# Input_Connector.net
KiCad netlist of a schematic drawn in Altium Designer
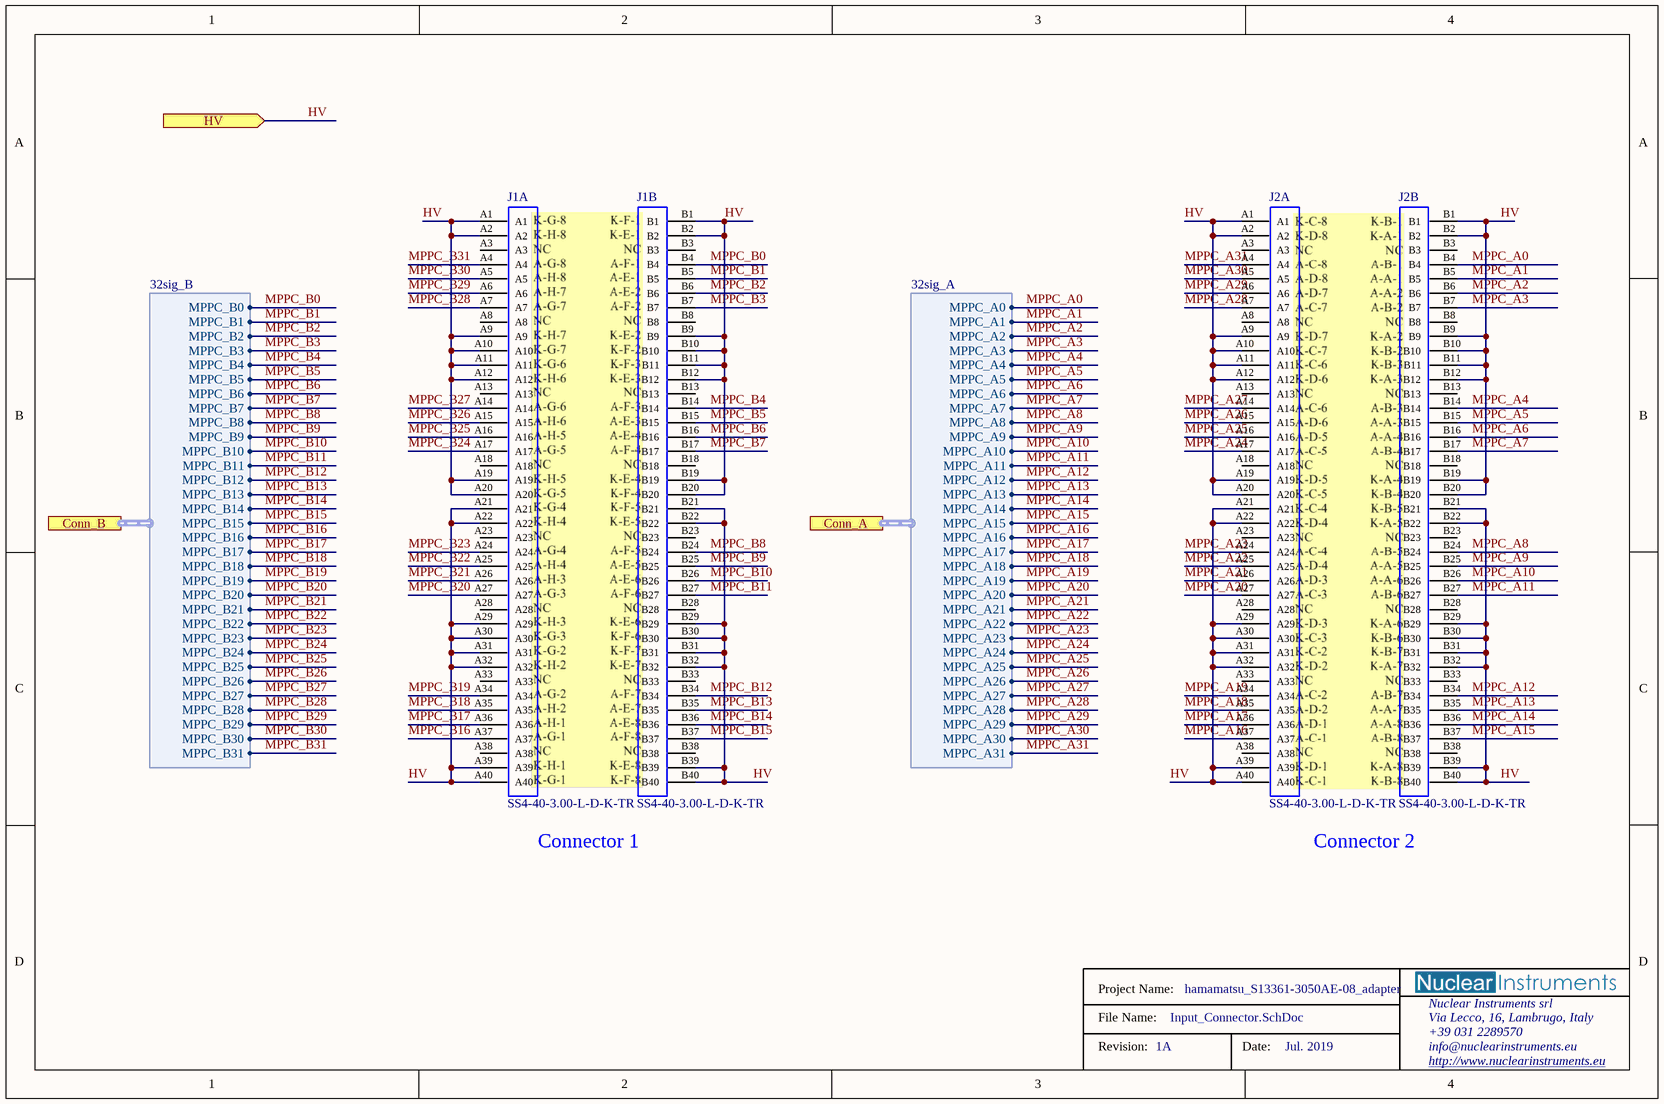
[diagram p0: Input_Connector.SchDoc]

(export (version "E")
  (design (tool "Eeschema 10.0.6"))
  (components
    (comp (ref "J1")
      (value "SS4-40-3.00-L-D-K-TR")
      (footprint "Samtec_SS4-40-3.00-L-D-K-TR")
      (description "ULTRA FINE PITCH SOCKET")
      (libsource (lib "Board_Board_Connectors__SARAversion-64") (part "Samtec_SS4-40-3.00-L-D-K-TR"))
    )
    (comp (ref "J2")
      (value "SS4-40-3.00-L-D-K-TR")
      (footprint "Samtec_SS4-40-3.00-L-D-K-TR")
      (description "ULTRA FINE PITCH SOCKET")
      (libsource (lib "Board_Board_Connectors__SARAversion-64") (part "Samtec_SS4-40-3.00-L-D-K-TR"))
    )
  )
  (nets
    (net (code "3") (name "/HV") (class "Default")
      (node (ref "J1") (pin "A1") (pinfunction "A1_A1") (pintype "passive"))
      (node (ref "J1") (pin "A10") (pinfunction "A10_A10") (pintype "passive"))
      (node (ref "J1") (pin "A11") (pinfunction "A11_A11") (pintype "passive"))
      (node (ref "J1") (pin "A12") (pinfunction "A12_A12") (pintype "passive"))
      (node (ref "J1") (pin "A19") (pinfunction "A19_A19") (pintype "passive"))
      (node (ref "J1") (pin "A2") (pinfunction "A2_A2") (pintype "passive"))
      (node (ref "J1") (pin "A20") (pinfunction "A20_A20") (pintype "passive"))
      (node (ref "J1") (pin "A21") (pinfunction "A21_A21") (pintype "passive"))
      (node (ref "J1") (pin "A22") (pinfunction "A22_A22") (pintype "passive"))
      (node (ref "J1") (pin "A29") (pinfunction "A29_A29") (pintype "passive"))
      (node (ref "J1") (pin "A30") (pinfunction "A30_A30") (pintype "passive"))
      (node (ref "J1") (pin "A31") (pinfunction "A31_A31") (pintype "passive"))
      (node (ref "J1") (pin "A32") (pinfunction "A32_A32") (pintype "passive"))
      (node (ref "J1") (pin "A39") (pinfunction "A39_A39") (pintype "passive"))
      (node (ref "J1") (pin "A40") (pinfunction "A40_A40") (pintype "passive"))
      (node (ref "J1") (pin "A9") (pinfunction "A9_A9") (pintype "passive"))
      (node (ref "J1") (pin "B1") (pinfunction "B1_B1") (pintype "passive"))
      (node (ref "J1") (pin "B10") (pinfunction "B10_B10") (pintype "passive"))
      (node (ref "J1") (pin "B11") (pinfunction "B11_B11") (pintype "passive"))
      (node (ref "J1") (pin "B12") (pinfunction "B12_B12") (pintype "passive"))
      (node (ref "J1") (pin "B19") (pinfunction "B19_B19") (pintype "passive"))
      (node (ref "J1") (pin "B2") (pinfunction "B2_B2") (pintype "passive"))
      (node (ref "J1") (pin "B20") (pinfunction "B20_B20") (pintype "passive"))
      (node (ref "J1") (pin "B21") (pinfunction "B21_B21") (pintype "passive"))
      (node (ref "J1") (pin "B22") (pinfunction "B22_B22") (pintype "passive"))
      (node (ref "J1") (pin "B29") (pinfunction "B29_B29") (pintype "passive"))
      (node (ref "J1") (pin "B30") (pinfunction "B30_B30") (pintype "passive"))
      (node (ref "J1") (pin "B31") (pinfunction "B31_B31") (pintype "passive"))
      (node (ref "J1") (pin "B32") (pinfunction "B32_B32") (pintype "passive"))
      (node (ref "J1") (pin "B39") (pinfunction "B39_B39") (pintype "passive"))
      (node (ref "J1") (pin "B40") (pinfunction "B40_B40") (pintype "passive"))
      (node (ref "J1") (pin "B9") (pinfunction "B9_B9") (pintype "passive"))
      (node (ref "J2") (pin "A1") (pinfunction "A1_A1") (pintype "passive"))
      (node (ref "J2") (pin "A10") (pinfunction "A10_A10") (pintype "passive"))
      (node (ref "J2") (pin "A11") (pinfunction "A11_A11") (pintype "passive"))
      (node (ref "J2") (pin "A12") (pinfunction "A12_A12") (pintype "passive"))
      (node (ref "J2") (pin "A19") (pinfunction "A19_A19") (pintype "passive"))
      (node (ref "J2") (pin "A2") (pinfunction "A2_A2") (pintype "passive"))
      (node (ref "J2") (pin "A20") (pinfunction "A20_A20") (pintype "passive"))
      (node (ref "J2") (pin "A21") (pinfunction "A21_A21") (pintype "passive"))
      (node (ref "J2") (pin "A22") (pinfunction "A22_A22") (pintype "passive"))
      (node (ref "J2") (pin "A29") (pinfunction "A29_A29") (pintype "passive"))
      (node (ref "J2") (pin "A30") (pinfunction "A30_A30") (pintype "passive"))
      (node (ref "J2") (pin "A31") (pinfunction "A31_A31") (pintype "passive"))
      (node (ref "J2") (pin "A32") (pinfunction "A32_A32") (pintype "passive"))
      (node (ref "J2") (pin "A39") (pinfunction "A39_A39") (pintype "passive"))
      (node (ref "J2") (pin "A40") (pinfunction "A40_A40") (pintype "passive"))
      (node (ref "J2") (pin "A9") (pinfunction "A9_A9") (pintype "passive"))
      (node (ref "J2") (pin "B1") (pinfunction "B1_B1") (pintype "passive"))
      (node (ref "J2") (pin "B10") (pinfunction "B10_B10") (pintype "passive"))
      (node (ref "J2") (pin "B11") (pinfunction "B11_B11") (pintype "passive"))
      (node (ref "J2") (pin "B12") (pinfunction "B12_B12") (pintype "passive"))
      (node (ref "J2") (pin "B19") (pinfunction "B19_B19") (pintype "passive"))
      (node (ref "J2") (pin "B2") (pinfunction "B2_B2") (pintype "passive"))
      (node (ref "J2") (pin "B20") (pinfunction "B20_B20") (pintype "passive"))
      (node (ref "J2") (pin "B21") (pinfunction "B21_B21") (pintype "passive"))
      (node (ref "J2") (pin "B22") (pinfunction "B22_B22") (pintype "passive"))
      (node (ref "J2") (pin "B29") (pinfunction "B29_B29") (pintype "passive"))
      (node (ref "J2") (pin "B30") (pinfunction "B30_B30") (pintype "passive"))
      (node (ref "J2") (pin "B31") (pinfunction "B31_B31") (pintype "passive"))
      (node (ref "J2") (pin "B32") (pinfunction "B32_B32") (pintype "passive"))
      (node (ref "J2") (pin "B39") (pinfunction "B39_B39") (pintype "passive"))
      (node (ref "J2") (pin "B40") (pinfunction "B40_B40") (pintype "passive"))
      (node (ref "J2") (pin "B9") (pinfunction "B9_B9") (pintype "passive"))
    )
    (net (code "4") (name "/MPPC_A0") (class "Default")
      (node (ref "J2") (pin "B4") (pinfunction "B4_B4") (pintype "passive"))
    )
    (net (code "5") (name "/MPPC_A1") (class "Default")
      (node (ref "J2") (pin "B5") (pinfunction "B5_B5") (pintype "passive"))
    )
    (net (code "6") (name "/MPPC_A2") (class "Default")
      (node (ref "J2") (pin "B6") (pinfunction "B6_B6") (pintype "passive"))
    )
    (net (code "7") (name "/MPPC_A3") (class "Default")
      (node (ref "J2") (pin "B7") (pinfunction "B7_B7") (pintype "passive"))
    )
    (net (code "8") (name "/MPPC_A4") (class "Default")
      (node (ref "J2") (pin "B14") (pinfunction "B14_B14") (pintype "passive"))
    )
    (net (code "9") (name "/MPPC_A5") (class "Default")
      (node (ref "J2") (pin "B15") (pinfunction "B15_B15") (pintype "passive"))
    )
    (net (code "10") (name "/MPPC_A6") (class "Default")
      (node (ref "J2") (pin "B16") (pinfunction "B16_B16") (pintype "passive"))
    )
    (net (code "11") (name "/MPPC_A7") (class "Default")
      (node (ref "J2") (pin "B17") (pinfunction "B17_B17") (pintype "passive"))
    )
    (net (code "12") (name "/MPPC_A8") (class "Default")
      (node (ref "J2") (pin "B24") (pinfunction "B24_B24") (pintype "passive"))
    )
    (net (code "13") (name "/MPPC_A9") (class "Default")
      (node (ref "J2") (pin "B25") (pinfunction "B25_B25") (pintype "passive"))
    )
    (net (code "14") (name "/MPPC_A10") (class "Default")
      (node (ref "J2") (pin "B26") (pinfunction "B26_B26") (pintype "passive"))
    )
    (net (code "15") (name "/MPPC_A11") (class "Default")
      (node (ref "J2") (pin "B27") (pinfunction "B27_B27") (pintype "passive"))
    )
    (net (code "16") (name "/MPPC_A12") (class "Default")
      (node (ref "J2") (pin "B34") (pinfunction "B34_B34") (pintype "passive"))
    )
    (net (code "17") (name "/MPPC_A13") (class "Default")
      (node (ref "J2") (pin "B35") (pinfunction "B35_B35") (pintype "passive"))
    )
    (net (code "18") (name "/MPPC_A14") (class "Default")
      (node (ref "J2") (pin "B36") (pinfunction "B36_B36") (pintype "passive"))
    )
    (net (code "19") (name "/MPPC_A15") (class "Default")
      (node (ref "J2") (pin "B37") (pinfunction "B37_B37") (pintype "passive"))
    )
    (net (code "20") (name "/MPPC_A16") (class "Default")
      (node (ref "J2") (pin "A37") (pinfunction "A37_A37") (pintype "passive"))
    )
    (net (code "21") (name "/MPPC_A17") (class "Default")
      (node (ref "J2") (pin "A36") (pinfunction "A36_A36") (pintype "passive"))
    )
    (net (code "22") (name "/MPPC_A18") (class "Default")
      (node (ref "J2") (pin "A35") (pinfunction "A35_A35") (pintype "passive"))
    )
    (net (code "23") (name "/MPPC_A19") (class "Default")
      (node (ref "J2") (pin "A34") (pinfunction "A34_A34") (pintype "passive"))
    )
    (net (code "24") (name "/MPPC_A20") (class "Default")
      (node (ref "J2") (pin "A27") (pinfunction "A27_A27") (pintype "passive"))
    )
    (net (code "25") (name "/MPPC_A21") (class "Default")
      (node (ref "J2") (pin "A26") (pinfunction "A26_A26") (pintype "passive"))
    )
    (net (code "26") (name "/MPPC_A22") (class "Default")
      (node (ref "J2") (pin "A25") (pinfunction "A25_A25") (pintype "passive"))
    )
    (net (code "27") (name "/MPPC_A23") (class "Default")
      (node (ref "J2") (pin "A24") (pinfunction "A24_A24") (pintype "passive"))
    )
    (net (code "28") (name "/MPPC_A24") (class "Default")
      (node (ref "J2") (pin "A17") (pinfunction "A17_A17") (pintype "passive"))
    )
    (net (code "29") (name "/MPPC_A25") (class "Default")
      (node (ref "J2") (pin "A16") (pinfunction "A16_A16") (pintype "passive"))
    )
    (net (code "30") (name "/MPPC_A26") (class "Default")
      (node (ref "J2") (pin "A15") (pinfunction "A15_A15") (pintype "passive"))
    )
    (net (code "31") (name "/MPPC_A27") (class "Default")
      (node (ref "J2") (pin "A14") (pinfunction "A14_A14") (pintype "passive"))
    )
    (net (code "32") (name "/MPPC_A28") (class "Default")
      (node (ref "J2") (pin "A7") (pinfunction "A7_A7") (pintype "passive"))
    )
    (net (code "33") (name "/MPPC_A29") (class "Default")
      (node (ref "J2") (pin "A6") (pinfunction "A6_A6") (pintype "passive"))
    )
    (net (code "34") (name "/MPPC_A30") (class "Default")
      (node (ref "J2") (pin "A5") (pinfunction "A5_A5") (pintype "passive"))
    )
    (net (code "35") (name "/MPPC_A31") (class "Default")
      (node (ref "J2") (pin "A4") (pinfunction "A4_A4") (pintype "passive"))
    )
    (net (code "36") (name "/MPPC_B0") (class "Default")
      (node (ref "J1") (pin "B4") (pinfunction "B4_B4") (pintype "passive"))
    )
    (net (code "37") (name "/MPPC_B1") (class "Default")
      (node (ref "J1") (pin "B5") (pinfunction "B5_B5") (pintype "passive"))
    )
    (net (code "38") (name "/MPPC_B2") (class "Default")
      (node (ref "J1") (pin "B6") (pinfunction "B6_B6") (pintype "passive"))
    )
    (net (code "39") (name "/MPPC_B3") (class "Default")
      (node (ref "J1") (pin "B7") (pinfunction "B7_B7") (pintype "passive"))
    )
    (net (code "40") (name "/MPPC_B4") (class "Default")
      (node (ref "J1") (pin "B14") (pinfunction "B14_B14") (pintype "passive"))
    )
    (net (code "41") (name "/MPPC_B5") (class "Default")
      (node (ref "J1") (pin "B15") (pinfunction "B15_B15") (pintype "passive"))
    )
    (net (code "42") (name "/MPPC_B6") (class "Default")
      (node (ref "J1") (pin "B16") (pinfunction "B16_B16") (pintype "passive"))
    )
    (net (code "43") (name "/MPPC_B7") (class "Default")
      (node (ref "J1") (pin "B17") (pinfunction "B17_B17") (pintype "passive"))
    )
    (net (code "44") (name "/MPPC_B8") (class "Default")
      (node (ref "J1") (pin "B24") (pinfunction "B24_B24") (pintype "passive"))
    )
    (net (code "45") (name "/MPPC_B9") (class "Default")
      (node (ref "J1") (pin "B25") (pinfunction "B25_B25") (pintype "passive"))
    )
    (net (code "46") (name "/MPPC_B10") (class "Default")
      (node (ref "J1") (pin "B26") (pinfunction "B26_B26") (pintype "passive"))
    )
    (net (code "47") (name "/MPPC_B11") (class "Default")
      (node (ref "J1") (pin "B27") (pinfunction "B27_B27") (pintype "passive"))
    )
    (net (code "48") (name "/MPPC_B12") (class "Default")
      (node (ref "J1") (pin "B34") (pinfunction "B34_B34") (pintype "passive"))
    )
    (net (code "49") (name "/MPPC_B13") (class "Default")
      (node (ref "J1") (pin "B35") (pinfunction "B35_B35") (pintype "passive"))
    )
    (net (code "50") (name "/MPPC_B14") (class "Default")
      (node (ref "J1") (pin "B36") (pinfunction "B36_B36") (pintype "passive"))
    )
    (net (code "51") (name "/MPPC_B15") (class "Default")
      (node (ref "J1") (pin "B37") (pinfunction "B37_B37") (pintype "passive"))
    )
    (net (code "52") (name "/MPPC_B16") (class "Default")
      (node (ref "J1") (pin "A37") (pinfunction "A37_A37") (pintype "passive"))
    )
    (net (code "53") (name "/MPPC_B17") (class "Default")
      (node (ref "J1") (pin "A36") (pinfunction "A36_A36") (pintype "passive"))
    )
    (net (code "54") (name "/MPPC_B18") (class "Default")
      (node (ref "J1") (pin "A35") (pinfunction "A35_A35") (pintype "passive"))
    )
    (net (code "55") (name "/MPPC_B19") (class "Default")
      (node (ref "J1") (pin "A34") (pinfunction "A34_A34") (pintype "passive"))
    )
    (net (code "56") (name "/MPPC_B20") (class "Default")
      (node (ref "J1") (pin "A27") (pinfunction "A27_A27") (pintype "passive"))
    )
    (net (code "57") (name "/MPPC_B21") (class "Default")
      (node (ref "J1") (pin "A26") (pinfunction "A26_A26") (pintype "passive"))
    )
    (net (code "58") (name "/MPPC_B22") (class "Default")
      (node (ref "J1") (pin "A25") (pinfunction "A25_A25") (pintype "passive"))
    )
    (net (code "59") (name "/MPPC_B23") (class "Default")
      (node (ref "J1") (pin "A24") (pinfunction "A24_A24") (pintype "passive"))
    )
    (net (code "60") (name "/MPPC_B24") (class "Default")
      (node (ref "J1") (pin "A17") (pinfunction "A17_A17") (pintype "passive"))
    )
    (net (code "61") (name "/MPPC_B25") (class "Default")
      (node (ref "J1") (pin "A16") (pinfunction "A16_A16") (pintype "passive"))
    )
    (net (code "62") (name "/MPPC_B26") (class "Default")
      (node (ref "J1") (pin "A15") (pinfunction "A15_A15") (pintype "passive"))
    )
    (net (code "63") (name "/MPPC_B27") (class "Default")
      (node (ref "J1") (pin "A14") (pinfunction "A14_A14") (pintype "passive"))
    )
    (net (code "64") (name "/MPPC_B28") (class "Default")
      (node (ref "J1") (pin "A7") (pinfunction "A7_A7") (pintype "passive"))
    )
    (net (code "65") (name "/MPPC_B29") (class "Default")
      (node (ref "J1") (pin "A6") (pinfunction "A6_A6") (pintype "passive"))
    )
    (net (code "66") (name "/MPPC_B30") (class "Default")
      (node (ref "J1") (pin "A5") (pinfunction "A5_A5") (pintype "passive"))
    )
    (net (code "67") (name "/MPPC_B31") (class "Default")
      (node (ref "J1") (pin "A4") (pinfunction "A4_A4") (pintype "passive"))
    )
    (net (code "70") (name "unconnected-(J1-PadA3)") (class "Default")
      (node (ref "J1") (pin "A3") (pinfunction "A3_A3") (pintype "passive"))
    )
    (net (code "71") (name "unconnected-(J1-PadA8)") (class "Default")
      (node (ref "J1") (pin "A8") (pinfunction "A8_A8") (pintype "passive"))
    )
    (net (code "72") (name "unconnected-(J1-PadA13)") (class "Default")
      (node (ref "J1") (pin "A13") (pinfunction "A13_A13") (pintype "passive"))
    )
    (net (code "73") (name "unconnected-(J1-PadA18)") (class "Default")
      (node (ref "J1") (pin "A18") (pinfunction "A18_A18") (pintype "passive"))
    )
    (net (code "74") (name "unconnected-(J1-PadA23)") (class "Default")
      (node (ref "J1") (pin "A23") (pinfunction "A23_A23") (pintype "passive"))
    )
    (net (code "75") (name "unconnected-(J1-PadA28)") (class "Default")
      (node (ref "J1") (pin "A28") (pinfunction "A28_A28") (pintype "passive"))
    )
    (net (code "76") (name "unconnected-(J1-PadA33)") (class "Default")
      (node (ref "J1") (pin "A33") (pinfunction "A33_A33") (pintype "passive"))
    )
    (net (code "77") (name "unconnected-(J1-PadA38)") (class "Default")
      (node (ref "J1") (pin "A38") (pinfunction "A38_A38") (pintype "passive"))
    )
    (net (code "78") (name "unconnected-(J1-PadB3)") (class "Default")
      (node (ref "J1") (pin "B3") (pinfunction "B3_B3") (pintype "passive"))
    )
    (net (code "79") (name "unconnected-(J1-PadB8)") (class "Default")
      (node (ref "J1") (pin "B8") (pinfunction "B8_B8") (pintype "passive"))
    )
    (net (code "80") (name "unconnected-(J1-PadB13)") (class "Default")
      (node (ref "J1") (pin "B13") (pinfunction "B13_B13") (pintype "passive"))
    )
    (net (code "81") (name "unconnected-(J1-PadB18)") (class "Default")
      (node (ref "J1") (pin "B18") (pinfunction "B18_B18") (pintype "passive"))
    )
    (net (code "82") (name "unconnected-(J1-PadB23)") (class "Default")
      (node (ref "J1") (pin "B23") (pinfunction "B23_B23") (pintype "passive"))
    )
    (net (code "83") (name "unconnected-(J1-PadB28)") (class "Default")
      (node (ref "J1") (pin "B28") (pinfunction "B28_B28") (pintype "passive"))
    )
    (net (code "84") (name "unconnected-(J1-PadB33)") (class "Default")
      (node (ref "J1") (pin "B33") (pinfunction "B33_B33") (pintype "passive"))
    )
    (net (code "85") (name "unconnected-(J1-PadB38)") (class "Default")
      (node (ref "J1") (pin "B38") (pinfunction "B38_B38") (pintype "passive"))
    )
    (net (code "86") (name "unconnected-(J2-PadA3)") (class "Default")
      (node (ref "J2") (pin "A3") (pinfunction "A3_A3") (pintype "passive"))
    )
    (net (code "87") (name "unconnected-(J2-PadA8)") (class "Default")
      (node (ref "J2") (pin "A8") (pinfunction "A8_A8") (pintype "passive"))
    )
    (net (code "88") (name "unconnected-(J2-PadA13)") (class "Default")
      (node (ref "J2") (pin "A13") (pinfunction "A13_A13") (pintype "passive"))
    )
    (net (code "89") (name "unconnected-(J2-PadA18)") (class "Default")
      (node (ref "J2") (pin "A18") (pinfunction "A18_A18") (pintype "passive"))
    )
    (net (code "90") (name "unconnected-(J2-PadA23)") (class "Default")
      (node (ref "J2") (pin "A23") (pinfunction "A23_A23") (pintype "passive"))
    )
    (net (code "91") (name "unconnected-(J2-PadA28)") (class "Default")
      (node (ref "J2") (pin "A28") (pinfunction "A28_A28") (pintype "passive"))
    )
    (net (code "92") (name "unconnected-(J2-PadA33)") (class "Default")
      (node (ref "J2") (pin "A33") (pinfunction "A33_A33") (pintype "passive"))
    )
    (net (code "93") (name "unconnected-(J2-PadA38)") (class "Default")
      (node (ref "J2") (pin "A38") (pinfunction "A38_A38") (pintype "passive"))
    )
    (net (code "94") (name "unconnected-(J2-PadB3)") (class "Default")
      (node (ref "J2") (pin "B3") (pinfunction "B3_B3") (pintype "passive"))
    )
    (net (code "95") (name "unconnected-(J2-PadB8)") (class "Default")
      (node (ref "J2") (pin "B8") (pinfunction "B8_B8") (pintype "passive"))
    )
    (net (code "96") (name "unconnected-(J2-PadB13)") (class "Default")
      (node (ref "J2") (pin "B13") (pinfunction "B13_B13") (pintype "passive"))
    )
    (net (code "97") (name "unconnected-(J2-PadB18)") (class "Default")
      (node (ref "J2") (pin "B18") (pinfunction "B18_B18") (pintype "passive"))
    )
    (net (code "98") (name "unconnected-(J2-PadB23)") (class "Default")
      (node (ref "J2") (pin "B23") (pinfunction "B23_B23") (pintype "passive"))
    )
    (net (code "99") (name "unconnected-(J2-PadB28)") (class "Default")
      (node (ref "J2") (pin "B28") (pinfunction "B28_B28") (pintype "passive"))
    )
    (net (code "100") (name "unconnected-(J2-PadB33)") (class "Default")
      (node (ref "J2") (pin "B33") (pinfunction "B33_B33") (pintype "passive"))
    )
    (net (code "101") (name "unconnected-(J2-PadB38)") (class "Default")
      (node (ref "J2") (pin "B38") (pinfunction "B38_B38") (pintype "passive"))
    )
  )
)
